# Alimentacion.net
KiCad netlist of a schematic drawn in Altium Designer
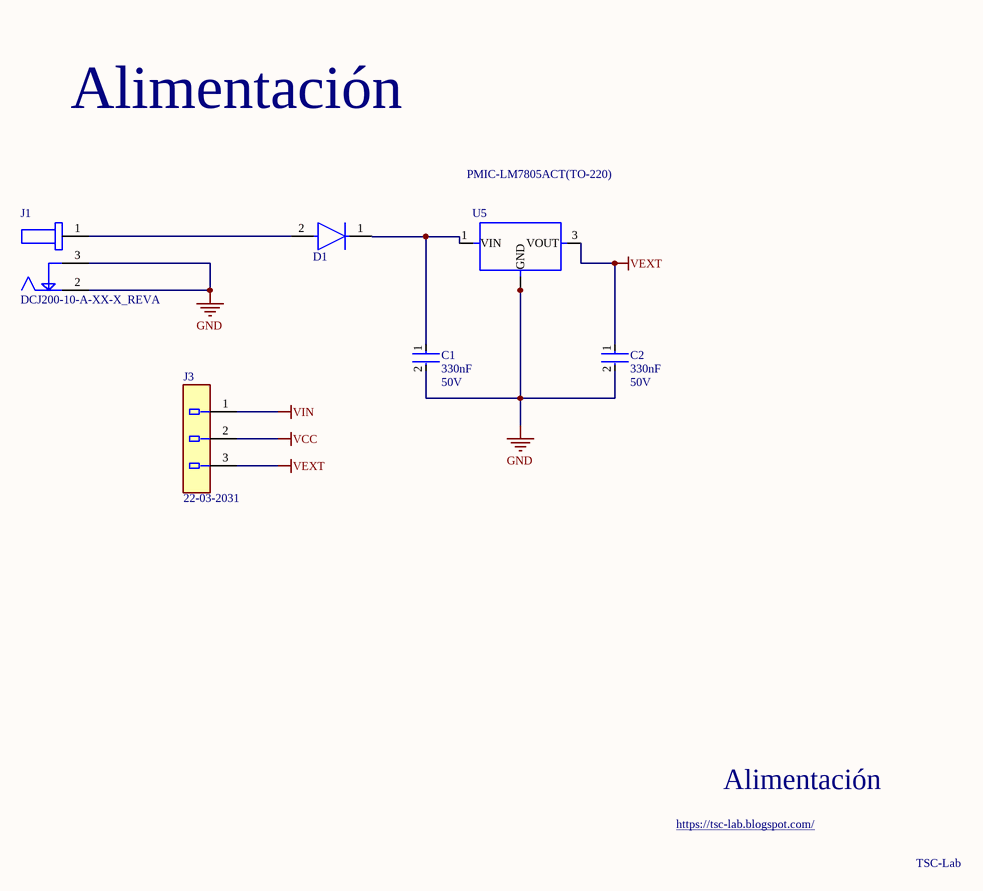
[diagram p0: Alimentacion.SchDoc]

(export (version "E")
  (design (tool "Eeschema 10.0.6"))
  (components
    (comp (ref "C1")
      (value "Cap_Kemet_C322C334M5U5TA7301_eec")
      (footprint "Kemet_C322C334M5U5TA7301_0")
      (description "CAP CER 0.33UF 50V Z5U RADIAL")
      (fields
        (field (name "CAPACITANCE") "330nF")
        (field (name "VOLTAGE") "50V")
        (field (name "PART NUMBER") "C322C334M5U5TA7301")
        (field (name "MANUFACTURER") "Kemet")
      )
      (libsource (lib "SnapEDA_Library") (part "Cap_Kemet_C322C334M5U5TA7301_eec"))
    )
    (comp (ref "C2")
      (value "Cap_Kemet_C322C334M5U5TA7301_eec")
      (footprint "Kemet_C322C334M5U5TA7301_0")
      (description "CAP CER 0.33UF 50V Z5U RADIAL")
      (fields
        (field (name "CAPACITANCE") "330nF")
        (field (name "VOLTAGE") "50V")
        (field (name "PART NUMBER") "C322C334M5U5TA7301")
        (field (name "MANUFACTURER") "Kemet")
      )
      (libsource (lib "SnapEDA_Library") (part "Cap_Kemet_C322C334M5U5TA7301_eec"))
    )
    (comp (ref "D1")
      (value "Diode_Vishay_1N4001E-E3-54_eec")
      (footprint "Vishay_1N4001E-E3-54_0")
      (description "DIODE GEN PURP 50V 1A DO204AL")
      (fields (field (name "PART NUMBER") "1N4001E-E3/54") (field (name "VOLTAGE") "50V"))
      (libsource (lib "SnapEDA_Library") (part "Diode_Vishay_1N4001E-E3-54_eec"))
    )
    (comp (ref "J1")
      (value "DCJ200-10-A-XX-X_REVA")
      (footprint "GCT_DCJ200-10-A-XX-X_REVA")
      (description "DC Power Jack, Thru-Hole, Horizontal, with Locating Pegs, D2.0mm")
      (fields (field (name "MF") "{'manufacturer': u'Global Connector Technology'}"))
      (libsource (lib "SnapEDA_Library") (part "DCJ200-10-A-XX-X_REVA"))
    )
    (comp (ref "J3")
      (value "Conn_Molex_22-03-2031_eec")
      (footprint "Molex_SD-4030-0001_0")
      (description "CONN HEADER 3POS .100 VERT TIN")
      (fields
        (field (name "PART NUMBER") "22-03-2031")
        (field (name "VOLTAGE") "150V")
        (field (name "MANUFACTURER") "Molex")
      )
      (libsource (lib "SnapEDA_Library") (part "Conn_Molex_22-03-2031_eec"))
    )
    (comp (ref "U5")
      (value "PMIC-LM7805ACT(TO-220)")
      (footprint "TO-220")
      (description "310030049")
      (fields (field (name "MP") "LM7805ACT") (field (name "MF") "{'manufacturer': u'ON Semiconductor'}"))
      (libsource (lib "SnapEDA_Library") (part "PMIC-LM7805ACT(TO-220)"))
    )
  )
  (nets
    (net (code "1") (name "GND") (class "Default")
      (node (ref "C1") (pin "2") (pinfunction "2_2") (pintype "passive"))
      (node (ref "C2") (pin "2") (pinfunction "2_2") (pintype "passive"))
      (node (ref "J1") (pin "2") (pinfunction "2_2") (pintype "passive"))
      (node (ref "J1") (pin "3") (pinfunction "3_3") (pintype "passive"))
      (node (ref "U5") (pin "2") (pinfunction "GND_2") (pintype "bidirectional"))
      (node (ref "U5") (pin "HEAT") (pinfunction "GND_HEAT") (pintype "bidirectional"))
    )
    (net (code "2") (name "Net-(D1-A)") (class "Default")
      (node (ref "D1") (pin "2") (pinfunction "A_2") (pintype "passive"))
      (node (ref "J1") (pin "1") (pinfunction "1_1") (pintype "passive"))
    )
    (net (code "3") (name "Net-(D1-C)") (class "Default")
      (node (ref "C1") (pin "1") (pinfunction "1_1") (pintype "passive"))
      (node (ref "D1") (pin "1") (pinfunction "C_1") (pintype "passive"))
      (node (ref "U5") (pin "1") (pinfunction "VIN_1") (pintype "bidirectional"))
    )
    (net (code "4") (name "VCC") (class "Default")
      (node (ref "J3") (pin "2") (pinfunction "2_2") (pintype "passive"))
    )
    (net (code "5") (name "VEXT") (class "Default")
      (node (ref "C2") (pin "1") (pinfunction "1_1") (pintype "passive"))
      (node (ref "J3") (pin "3") (pinfunction "3_3") (pintype "passive"))
      (node (ref "U5") (pin "3") (pinfunction "VOUT_3") (pintype "bidirectional"))
    )
    (net (code "6") (name "VIN") (class "Default")
      (node (ref "J3") (pin "1") (pinfunction "1_1") (pintype "passive"))
    )
  )
)
